# Battery_Module.net
KiCad netlist of a schematic drawn in Altium Designer
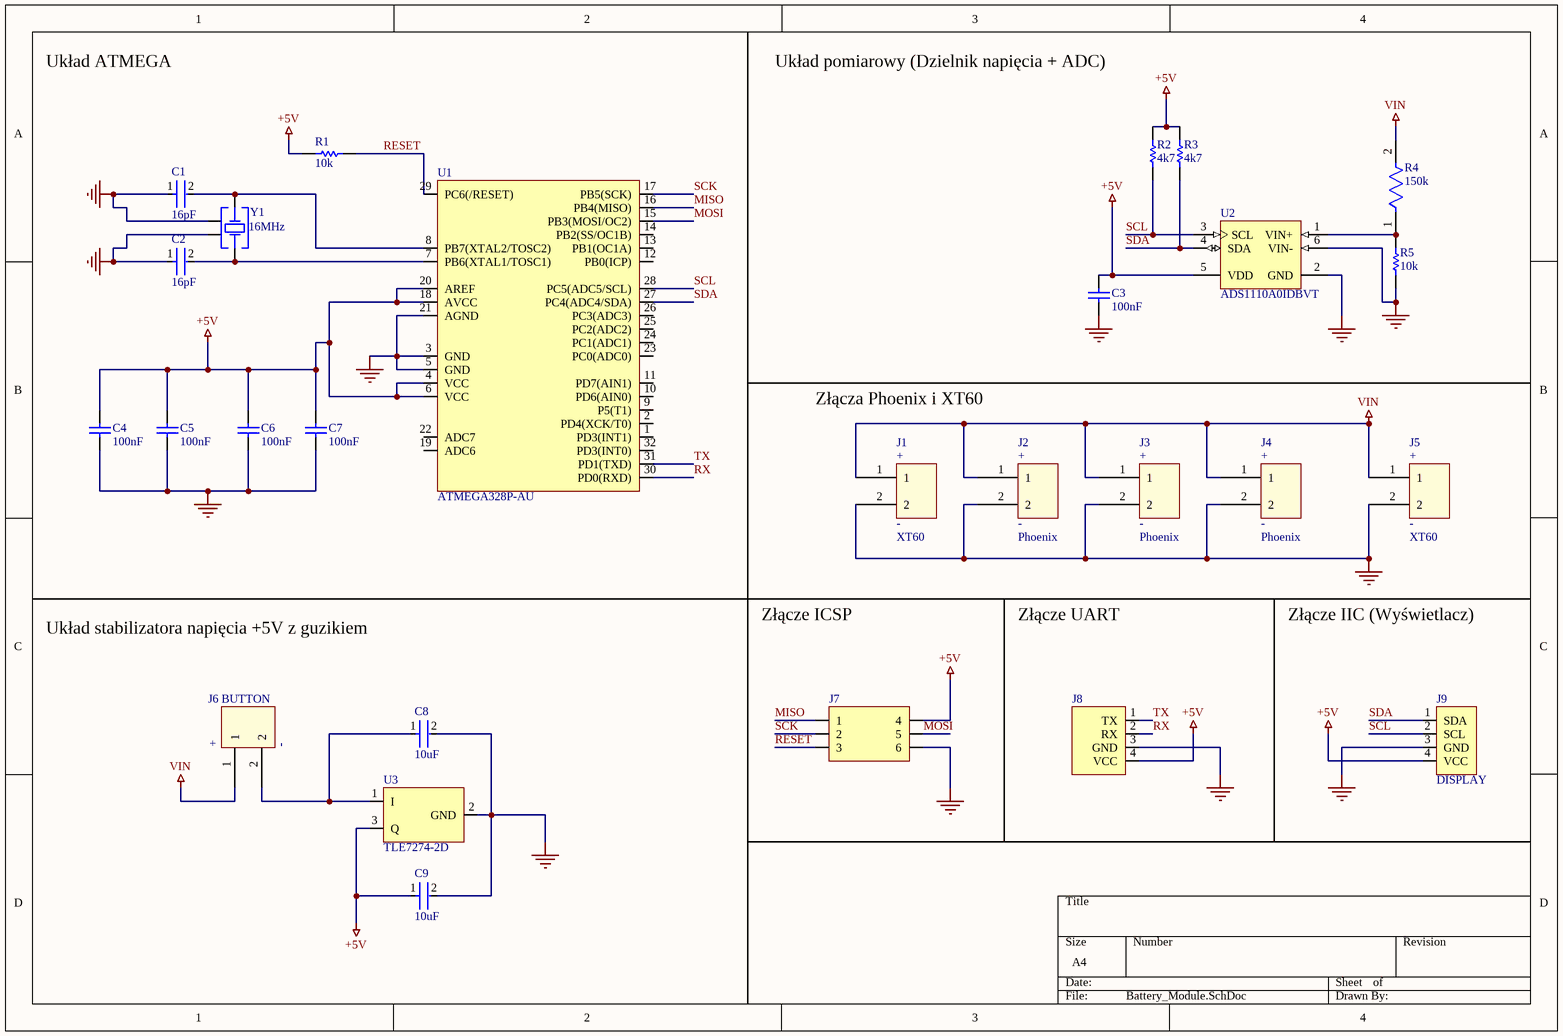
[diagram p0: Battery_Module.SchDoc]

(export (version "E")
  (design (tool "Eeschema 10.0.6"))
  (components
    (comp (ref "C1")
      (value "16pF")
      (footprint "FP-C0805C-DN-IPC_A")
      (description "C0805C160J5GACTU\r\nCAP CER 16PF 50V NP0 0805")
      (fields (field (name "MANUFACTURER PART NUMBER") "C0805C160J5GACTU") (field (name "TOLERANCE") "0.05"))
      (libsource (lib "Altium Content Vault") (part "b4654b650e69147ec39a6b967a45e02"))
    )
    (comp (ref "C2")
      (value "16pF")
      (footprint "FP-C0805C-DN-IPC_A")
      (description "C0805C160J5GACTU\r\nCAP CER 16PF 50V NP0 0805")
      (fields (field (name "MANUFACTURER PART NUMBER") "C0805C160J5GACTU") (field (name "TOLERANCE") "0.05"))
      (libsource (lib "Altium Content Vault") (part "b4654b650e69147ec39a6b967a45e02"))
    )
    (comp (ref "C3")
      (value "100nF")
      (footprint "CAPC2013X140X50ML20T25")
      (fields
        (field (name "MANUFACTURER") "AVX Interconnect / Elco")
        (field (name "PART NUMBER") "08055F104KAT2A")
      )
      (libsource (lib "Altium Content Vault") (part "CAP"))
    )
    (comp (ref "C4")
      (value "100nF")
      (footprint "CAPC2013X140X50ML20T25")
      (fields
        (field (name "MANUFACTURER") "AVX Interconnect / Elco")
        (field (name "PART NUMBER") "08055F104KAT2A")
      )
      (libsource (lib "Altium Content Vault") (part "CAP"))
    )
    (comp (ref "C5")
      (value "100nF")
      (footprint "CAPC2013X140X50ML20T25")
      (fields
        (field (name "MANUFACTURER") "AVX Interconnect / Elco")
        (field (name "PART NUMBER") "08055F104KAT2A")
      )
      (libsource (lib "Altium Content Vault") (part "CAP"))
    )
    (comp (ref "C6")
      (value "100nF")
      (footprint "CAPC2013X140X50ML20T25")
      (fields
        (field (name "MANUFACTURER") "AVX Interconnect / Elco")
        (field (name "PART NUMBER") "08055F104KAT2A")
      )
      (libsource (lib "Altium Content Vault") (part "CAP"))
    )
    (comp (ref "C7")
      (value "100nF")
      (footprint "CAPC2013X140X50ML20T25")
      (fields
        (field (name "MANUFACTURER") "AVX Interconnect / Elco")
        (field (name "PART NUMBER") "08055F104KAT2A")
      )
      (libsource (lib "Altium Content Vault") (part "CAP"))
    )
    (comp (ref "C8")
      (value "10uF")
      (footprint "FP-GRM21B-0_1-IPC_A")
      (description "Chip Multilayer Ceramic Capacitors for General Purpose, 0805, 10uF, X6S, 22%, 10%, 10V")
      (fields (field (name "VOLTAGE") "10V") (field (name "TOLERANCE") "10%"))
      (libsource (lib "Altium Content Vault") (part "b4654b650e69147ec39a6b967a45e02"))
    )
    (comp (ref "C9")
      (value "10uF")
      (footprint "FP-GRM21B-0_1-IPC_A")
      (description "Chip Multilayer Ceramic Capacitors for General Purpose, 0805, 10uF, X6S, 22%, 10%, 10V")
      (fields (field (name "VOLTAGE") "10V") (field (name "TOLERANCE") "10%"))
      (libsource (lib "Altium Content Vault") (part "b4654b650e69147ec39a6b967a45e02"))
    )
    (comp (ref "J1")
      (value "XT60")
      (footprint "XT60_FEMALE_PANEL")
      (libsource (lib "") (part "Connector_2_1"))
    )
    (comp (ref "J2") (value "Phoenix") (footprint "Phoenix") (libsource (lib "") (part "Connector_2_1")))
    (comp (ref "J3") (value "Phoenix") (footprint "Phoenix") (libsource (lib "") (part "Connector_2_1")))
    (comp (ref "J4") (value "Phoenix") (footprint "Phoenix") (libsource (lib "") (part "Connector_2_1")))
    (comp (ref "J5")
      (value "XT60")
      (footprint "XT60_FEMALE_PANEL")
      (libsource (lib "") (part "Connector_2_1"))
    )
    (comp (ref "J6")
      (value "BUTTON")
      (footprint "HEADER1x2")
      (libsource (lib "XT+PHOENIX") (part "Connector_2"))
    )
    (comp (ref "J7")
      (value "~")
      (footprint "Header2x3 - duplicate")
      (libsource (lib "Uklady_i_zlacza") (part "Header 2x3"))
    )
    (comp (ref "J8") (value "~") (footprint "Header1x4") (libsource (lib "Uklady_i_zlacza") (part "UART")))
    (comp (ref "J9")
      (value "DISPLAY")
      (footprint "Header1x4")
      (libsource (lib "Uklady_i_zlacza") (part "IIC for Display"))
    )
    (comp (ref "R1")
      (value "10k")
      (footprint "RESC2013X60X35ML10T20")
      (fields (field (name "MANUFACTURER") "Yageo"))
      (libsource (lib "Altium Content Vault") (part "RES-2"))
    )
    (comp (ref "R2")
      (value "4k7")
      (footprint "YAGO-RC0805_M")
      (fields
        (field (name "TOLERANCE") "+/- 1%")
        (field (name "PARTNUMBER") "RC0805FR-074K7L")
        (field (name "POWER") "0.125 W")
      )
      (libsource (lib "Altium Content Vault") (part "YAGO-RES-2"))
    )
    (comp (ref "R3")
      (value "4k7")
      (footprint "YAGO-RC0805_M")
      (fields
        (field (name "TOLERANCE") "+/- 1%")
        (field (name "PARTNUMBER") "RC0805FR-074K7L")
        (field (name "POWER") "0.125 W")
      )
      (libsource (lib "Altium Content Vault") (part "YAGO-RES-2"))
    )
    (comp (ref "R4")
      (value "150k")
      (footprint "FP-ERA6A-MFG")
      (description "ERA-6AEB154V\r\nRES 150K OHM 0.1% 1/8W 0805")
      (fields (field (name "TOLERANCE") "0.1%"))
      (libsource (lib "Altium Content Vault") (part "1029c3af85768c4190bb7ad29bc67b5"))
    )
    (comp (ref "R5")
      (value "10k")
      (footprint "RESC2013X60X35ML10T20")
      (fields (field (name "MANUFACTURER") "Yageo"))
      (libsource (lib "Altium Content Vault") (part "RES-2"))
    )
    (comp (ref "U1")
      (value "ATMEGA328P-AU")
      (footprint "ATMEGA328P-AU")
      (description "8-bit Microcontrollers - MCU 32KB In-system Flash 20MHz 1.8V-5.5V")
      (libsource (lib "Uklady_i_zlacza") (part "ATMEGA328P-AU"))
    )
    (comp (ref "U2")
      (value "ADS1110A0IDBVT")
      (footprint "TI-DBV6_N")
      (fields (field (name "MANUFACTURER") "Texas Instruments"))
      (libsource (lib "Altium Content Vault") (part "TI-ADS1XX0XDBV6"))
    )
    (comp (ref "U3")
      (value "TLE7274-2D")
      (footprint "TO228P998X235-3N-2-V")
      (libsource (lib "Uklady_i_zlacza") (part "TLE7274-2D"))
    )
    (comp (ref "Y1")
      (value "16MHz")
      (footprint "WE-XTAL_CFPX-180")
      (description "830035264 WE-XTAL Quartz Crystal")
      (libsource (lib "Altium Content Vault") (part "WE-XTAL_CFPX-180"))
    )
  )
  (nets
    (net (code "1") (name "+5V") (class "Default")
      (node (ref "C3") (pin "2") (pinfunction "2_2") (pintype "passive"))
      (node (ref "C4") (pin "1") (pinfunction "1_1") (pintype "passive"))
      (node (ref "C5") (pin "1") (pinfunction "1_1") (pintype "passive"))
      (node (ref "C6") (pin "1") (pinfunction "1_1") (pintype "passive"))
      (node (ref "C7") (pin "1") (pinfunction "1_1") (pintype "passive"))
      (node (ref "C9") (pin "1") (pinfunction "1_1") (pintype "passive"))
      (node (ref "J7") (pin "4") (pinfunction "4_4") (pintype "passive"))
      (node (ref "J8") (pin "4") (pinfunction "VCC_4") (pintype "passive"))
      (node (ref "J9") (pin "4") (pinfunction "VCC_4") (pintype "passive"))
      (node (ref "R1") (pin "2") (pinfunction "2_2") (pintype "passive"))
      (node (ref "R2") (pin "2") (pinfunction "2_2") (pintype "passive"))
      (node (ref "R3") (pin "2") (pinfunction "2_2") (pintype "passive"))
      (node (ref "U1") (pin "18") (pinfunction "AVCC_18") (pintype "passive"))
      (node (ref "U1") (pin "20") (pinfunction "AREF_20") (pintype "passive"))
      (node (ref "U1") (pin "4") (pinfunction "VCC_4") (pintype "passive"))
      (node (ref "U1") (pin "6") (pinfunction "VCC_6") (pintype "passive"))
      (node (ref "U2") (pin "5") (pinfunction "VDD_5") (pintype "power_in"))
      (node (ref "U3") (pin "3") (pinfunction "Q_3") (pintype "passive"))
    )
    (net (code "2") (name "/MISO") (class "Default")
      (node (ref "J7") (pin "1") (pinfunction "1_1") (pintype "passive"))
      (node (ref "U1") (pin "16") (pinfunction "PB4(MISO)_16") (pintype "passive"))
    )
    (net (code "3") (name "/MOSI") (class "Default")
      (node (ref "J7") (pin "5") (pinfunction "5_5") (pintype "passive"))
      (node (ref "U1") (pin "15") (pinfunction "PB3(MOSI/OC2)_15") (pintype "passive"))
    )
    (net (code "4") (name "/RESET") (class "Default")
      (node (ref "J7") (pin "3") (pinfunction "3_3") (pintype "passive"))
      (node (ref "R1") (pin "1") (pinfunction "1_1") (pintype "passive"))
      (node (ref "U1") (pin "29") (pinfunction "PC6(/RESET)_29") (pintype "passive"))
    )
    (net (code "5") (name "/RX") (class "Default")
      (node (ref "J8") (pin "2") (pinfunction "RX_2") (pintype "passive"))
      (node (ref "U1") (pin "30") (pinfunction "PD0(RXD)_30") (pintype "passive"))
    )
    (net (code "6") (name "/SCK") (class "Default")
      (node (ref "J7") (pin "2") (pinfunction "2_2") (pintype "passive"))
      (node (ref "U1") (pin "17") (pinfunction "PB5(SCK)_17") (pintype "passive"))
    )
    (net (code "7") (name "/SCL") (class "Default")
      (node (ref "J9") (pin "2") (pinfunction "SCL_2") (pintype "passive"))
      (node (ref "R2") (pin "1") (pinfunction "1_1") (pintype "passive"))
      (node (ref "U1") (pin "28") (pinfunction "PC5(ADC5/SCL)_28") (pintype "passive"))
      (node (ref "U2") (pin "3") (pinfunction "SCL_3") (pintype "input"))
    )
    (net (code "8") (name "/SDA") (class "Default")
      (node (ref "J9") (pin "1") (pinfunction "SDA_1") (pintype "passive"))
      (node (ref "R3") (pin "1") (pinfunction "1_1") (pintype "passive"))
      (node (ref "U1") (pin "27") (pinfunction "PC4(ADC4/SDA)_27") (pintype "passive"))
      (node (ref "U2") (pin "4") (pinfunction "SDA_4") (pintype "bidirectional"))
    )
    (net (code "9") (name "/TX") (class "Default")
      (node (ref "J8") (pin "1") (pinfunction "TX_1") (pintype "passive"))
      (node (ref "U1") (pin "31") (pinfunction "PD1(TXD)_31") (pintype "passive"))
    )
    (net (code "10") (name "GND") (class "Default")
      (node (ref "C1") (pin "1") (pinfunction "1_1") (pintype "passive"))
      (node (ref "C2") (pin "1") (pinfunction "1_1") (pintype "passive"))
      (node (ref "C3") (pin "1") (pinfunction "1_1") (pintype "passive"))
      (node (ref "C4") (pin "2") (pinfunction "2_2") (pintype "passive"))
      (node (ref "C5") (pin "2") (pinfunction "2_2") (pintype "passive"))
      (node (ref "C6") (pin "2") (pinfunction "2_2") (pintype "passive"))
      (node (ref "C7") (pin "2") (pinfunction "2_2") (pintype "passive"))
      (node (ref "C8") (pin "2") (pinfunction "2_2") (pintype "passive"))
      (node (ref "C9") (pin "2") (pinfunction "2_2") (pintype "passive"))
      (node (ref "J1") (pin "2") (pinfunction "2_2") (pintype "passive"))
      (node (ref "J2") (pin "2") (pinfunction "2_2") (pintype "passive"))
      (node (ref "J3") (pin "2") (pinfunction "2_2") (pintype "passive"))
      (node (ref "J4") (pin "2") (pinfunction "2_2") (pintype "passive"))
      (node (ref "J5") (pin "2") (pinfunction "2_2") (pintype "passive"))
      (node (ref "J7") (pin "6") (pinfunction "6_6") (pintype "passive"))
      (node (ref "J8") (pin "3") (pinfunction "GND_3") (pintype "passive"))
      (node (ref "J9") (pin "3") (pinfunction "GND_3") (pintype "passive"))
      (node (ref "R5") (pin "1") (pinfunction "1_1") (pintype "passive"))
      (node (ref "U1") (pin "21") (pinfunction "AGND_21") (pintype "passive"))
      (node (ref "U1") (pin "3") (pinfunction "GND_3") (pintype "passive"))
      (node (ref "U1") (pin "5") (pinfunction "GND_5") (pintype "passive"))
      (node (ref "U2") (pin "2") (pinfunction "GND_2") (pintype "power_in"))
      (node (ref "U2") (pin "6") (pinfunction "VIN-_6") (pintype "input"))
      (node (ref "U3") (pin "2") (pinfunction "GND_2") (pintype "passive"))
      (node (ref "Y1") (pin "2") (pinfunction "GND&Lid_2") (pintype "passive"))
      (node (ref "Y1") (pin "4") (pinfunction "GND&Lid_4") (pintype "passive"))
    )
    (net (code "11") (name "Net-(U1-PB6(XTAL1{slash}TOSC1))") (class "Default")
      (node (ref "C2") (pin "2") (pinfunction "2_2") (pintype "passive"))
      (node (ref "U1") (pin "7") (pinfunction "PB6(XTAL1/TOSC1)_7") (pintype "passive"))
      (node (ref "Y1") (pin "3") (pinfunction "Crystal_3") (pintype "passive"))
    )
    (net (code "12") (name "Net-(U1-PB7(XTAL2{slash}TOSC2))") (class "Default")
      (node (ref "C1") (pin "2") (pinfunction "2_2") (pintype "passive"))
      (node (ref "U1") (pin "8") (pinfunction "PB7(XTAL2/TOSC2)_8") (pintype "passive"))
      (node (ref "Y1") (pin "1") (pinfunction "Crystal_1") (pintype "passive"))
    )
    (net (code "13") (name "Net-(U2-VIN+)") (class "Default")
      (node (ref "R4") (pin "1") (pinfunction "1_1") (pintype "passive"))
      (node (ref "R5") (pin "2") (pinfunction "2_2") (pintype "passive"))
      (node (ref "U2") (pin "1") (pinfunction "VIN+_1") (pintype "input"))
    )
    (net (code "14") (name "Net-(U3-I)") (class "Default")
      (node (ref "C8") (pin "1") (pinfunction "1_1") (pintype "passive"))
      (node (ref "J6") (pin "2") (pinfunction "2_2") (pintype "passive"))
      (node (ref "U3") (pin "1") (pinfunction "I_1") (pintype "passive"))
    )
    (net (code "15") (name "VIN") (class "Default")
      (node (ref "J1") (pin "1") (pinfunction "1_1") (pintype "passive"))
      (node (ref "J2") (pin "1") (pinfunction "1_1") (pintype "passive"))
      (node (ref "J3") (pin "1") (pinfunction "1_1") (pintype "passive"))
      (node (ref "J4") (pin "1") (pinfunction "1_1") (pintype "passive"))
      (node (ref "J5") (pin "1") (pinfunction "1_1") (pintype "passive"))
      (node (ref "J6") (pin "1") (pinfunction "1_1") (pintype "passive"))
      (node (ref "R4") (pin "2") (pinfunction "2_2") (pintype "passive"))
    )
    (net (code "16") (name "unconnected-(U1-ADC6-Pad19)") (class "Default")
      (node (ref "U1") (pin "19") (pinfunction "ADC6_19") (pintype "passive"))
    )
    (net (code "17") (name "unconnected-(U1-ADC7-Pad22)") (class "Default")
      (node (ref "U1") (pin "22") (pinfunction "ADC7_22") (pintype "passive"))
    )
    (net (code "18") (name "unconnected-(U1-P5(T1)-Pad9)") (class "Default")
      (node (ref "U1") (pin "9") (pinfunction "P5(T1)_9") (pintype "passive"))
    )
    (net (code "19") (name "unconnected-(U1-PB0(ICP)-Pad12)") (class "Default")
      (node (ref "U1") (pin "12") (pinfunction "PB0(ICP)_12") (pintype "passive"))
    )
    (net (code "20") (name "unconnected-(U1-PB1(OC1A)-Pad13)") (class "Default")
      (node (ref "U1") (pin "13") (pinfunction "PB1(OC1A)_13") (pintype "passive"))
    )
    (net (code "21") (name "unconnected-(U1-PB2(SS{slash}OC1B)-Pad14)") (class "Default")
      (node (ref "U1") (pin "14") (pinfunction "PB2(SS/OC1B)_14") (pintype "passive"))
    )
    (net (code "22") (name "unconnected-(U1-PC0(ADC0)-Pad23)") (class "Default")
      (node (ref "U1") (pin "23") (pinfunction "PC0(ADC0)_23") (pintype "passive"))
    )
    (net (code "23") (name "unconnected-(U1-PC1(ADC1)-Pad24)") (class "Default")
      (node (ref "U1") (pin "24") (pinfunction "PC1(ADC1)_24") (pintype "passive"))
    )
    (net (code "24") (name "unconnected-(U1-PC2(ADC2)-Pad25)") (class "Default")
      (node (ref "U1") (pin "25") (pinfunction "PC2(ADC2)_25") (pintype "passive"))
    )
    (net (code "25") (name "unconnected-(U1-PC3(ADC3)-Pad26)") (class "Default")
      (node (ref "U1") (pin "26") (pinfunction "PC3(ADC3)_26") (pintype "passive"))
    )
    (net (code "26") (name "unconnected-(U1-PD3(INT0)-Pad32)") (class "Default")
      (node (ref "U1") (pin "32") (pinfunction "PD3(INT0)_32") (pintype "passive"))
    )
    (net (code "27") (name "unconnected-(U1-PD3(INT1)-Pad1)") (class "Default")
      (node (ref "U1") (pin "1") (pinfunction "PD3(INT1)_1") (pintype "passive"))
    )
    (net (code "28") (name "unconnected-(U1-PD4(XCK{slash}T0)-Pad2)") (class "Default")
      (node (ref "U1") (pin "2") (pinfunction "PD4(XCK/T0)_2") (pintype "passive"))
    )
    (net (code "29") (name "unconnected-(U1-PD6(AIN0)-Pad10)") (class "Default")
      (node (ref "U1") (pin "10") (pinfunction "PD6(AIN0)_10") (pintype "passive"))
    )
    (net (code "30") (name "unconnected-(U1-PD7(AIN1)-Pad11)") (class "Default")
      (node (ref "U1") (pin "11") (pinfunction "PD7(AIN1)_11") (pintype "passive"))
    )
  )
)
